# PDMC-S06-V00-Connector.net
KiCad netlist of a schematic drawn in Altium Designer
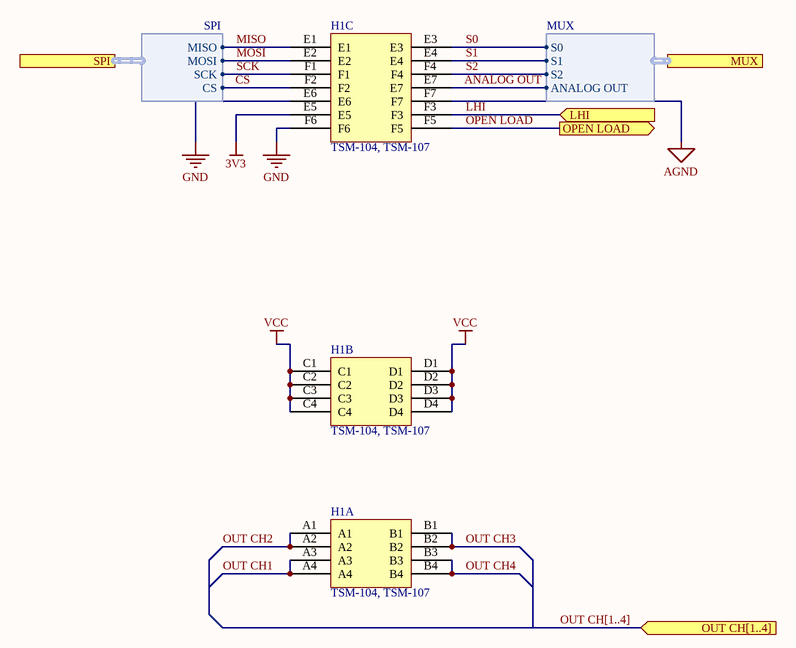
[diagram p0: PDMC-S06-V00-Connector.SchDoc]

(export (version "E")
  (design (tool "Eeschema 10.0.6"))
  (components
    (comp (ref "H1")
      (value "TSM-104, TSM-107")
      (footprint "TSM-104, TSM-107")
      (description "CONN HEADER SMD R/A 8POS and 14POS 2.54MM")
      (libsource (lib "PDM-CARD-SCHLib-V00") (part "TSM-104, TSM-107"))
    )
  )
  (nets
    (net (code "3") (name "/ANALOG OUT") (class "Default")
      (node (ref "H1") (pin "E7") (pinfunction "E7_E7") (pintype "passive"))
    )
    (net (code "4") (name "/CS") (class "Default")
      (node (ref "H1") (pin "F2") (pinfunction "F2_F2") (pintype "passive"))
    )
    (net (code "5") (name "/LHI") (class "Default")
      (node (ref "H1") (pin "F3") (pinfunction "F3_F3") (pintype "passive"))
    )
    (net (code "6") (name "/MISO") (class "Default")
      (node (ref "H1") (pin "E1") (pinfunction "E1_E1") (pintype "passive"))
    )
    (net (code "7") (name "/MOSI") (class "Default")
      (node (ref "H1") (pin "E2") (pinfunction "E2_E2") (pintype "passive"))
    )
    (net (code "8") (name "/OPEN LOAD") (class "Default")
      (node (ref "H1") (pin "F5") (pinfunction "F5_F5") (pintype "passive"))
    )
    (net (code "9") (name "/OUT CH1") (class "Default")
      (node (ref "H1") (pin "A3") (pinfunction "A3_A3") (pintype "passive"))
      (node (ref "H1") (pin "A4") (pinfunction "A4_A4") (pintype "passive"))
    )
    (net (code "10") (name "/OUT CH2") (class "Default")
      (node (ref "H1") (pin "A1") (pinfunction "A1_A1") (pintype "passive"))
      (node (ref "H1") (pin "A2") (pinfunction "A2_A2") (pintype "passive"))
    )
    (net (code "11") (name "/OUT CH3") (class "Default")
      (node (ref "H1") (pin "B1") (pinfunction "B1_B1") (pintype "passive"))
      (node (ref "H1") (pin "B2") (pinfunction "B2_B2") (pintype "passive"))
    )
    (net (code "12") (name "/OUT CH4") (class "Default")
      (node (ref "H1") (pin "B3") (pinfunction "B3_B3") (pintype "passive"))
      (node (ref "H1") (pin "B4") (pinfunction "B4_B4") (pintype "passive"))
    )
    (net (code "13") (name "/S0") (class "Default")
      (node (ref "H1") (pin "E3") (pinfunction "E3_E3") (pintype "passive"))
    )
    (net (code "14") (name "/S1") (class "Default")
      (node (ref "H1") (pin "E4") (pinfunction "E4_E4") (pintype "passive"))
    )
    (net (code "15") (name "/S2") (class "Default")
      (node (ref "H1") (pin "F4") (pinfunction "F4_F4") (pintype "passive"))
    )
    (net (code "16") (name "/SCK") (class "Default")
      (node (ref "H1") (pin "F1") (pinfunction "F1_F1") (pintype "passive"))
    )
    (net (code "20") (name "3V3") (class "Default")
      (node (ref "H1") (pin "E5") (pinfunction "E5_E5") (pintype "passive"))
    )
    (net (code "21") (name "AGND") (class "Default")
      (node (ref "H1") (pin "F7") (pinfunction "F7_F7") (pintype "passive"))
    )
    (net (code "22") (name "GND") (class "Default")
      (node (ref "H1") (pin "E6") (pinfunction "E6_E6") (pintype "passive"))
      (node (ref "H1") (pin "F6") (pinfunction "F6_F6") (pintype "passive"))
    )
    (net (code "23") (name "VCC") (class "Default")
      (node (ref "H1") (pin "C1") (pinfunction "C1_C1") (pintype "passive"))
      (node (ref "H1") (pin "C2") (pinfunction "C2_C2") (pintype "passive"))
      (node (ref "H1") (pin "C3") (pinfunction "C3_C3") (pintype "passive"))
      (node (ref "H1") (pin "C4") (pinfunction "C4_C4") (pintype "passive"))
      (node (ref "H1") (pin "D1") (pinfunction "D1_D1") (pintype "passive"))
      (node (ref "H1") (pin "D2") (pinfunction "D2_D2") (pintype "passive"))
      (node (ref "H1") (pin "D3") (pinfunction "D3_D3") (pintype "passive"))
      (node (ref "H1") (pin "D4") (pinfunction "D4_D4") (pintype "passive"))
    )
  )
)
